# cc1200layoutv_2.net
KiCad netlist of a schematic drawn in EAGLE
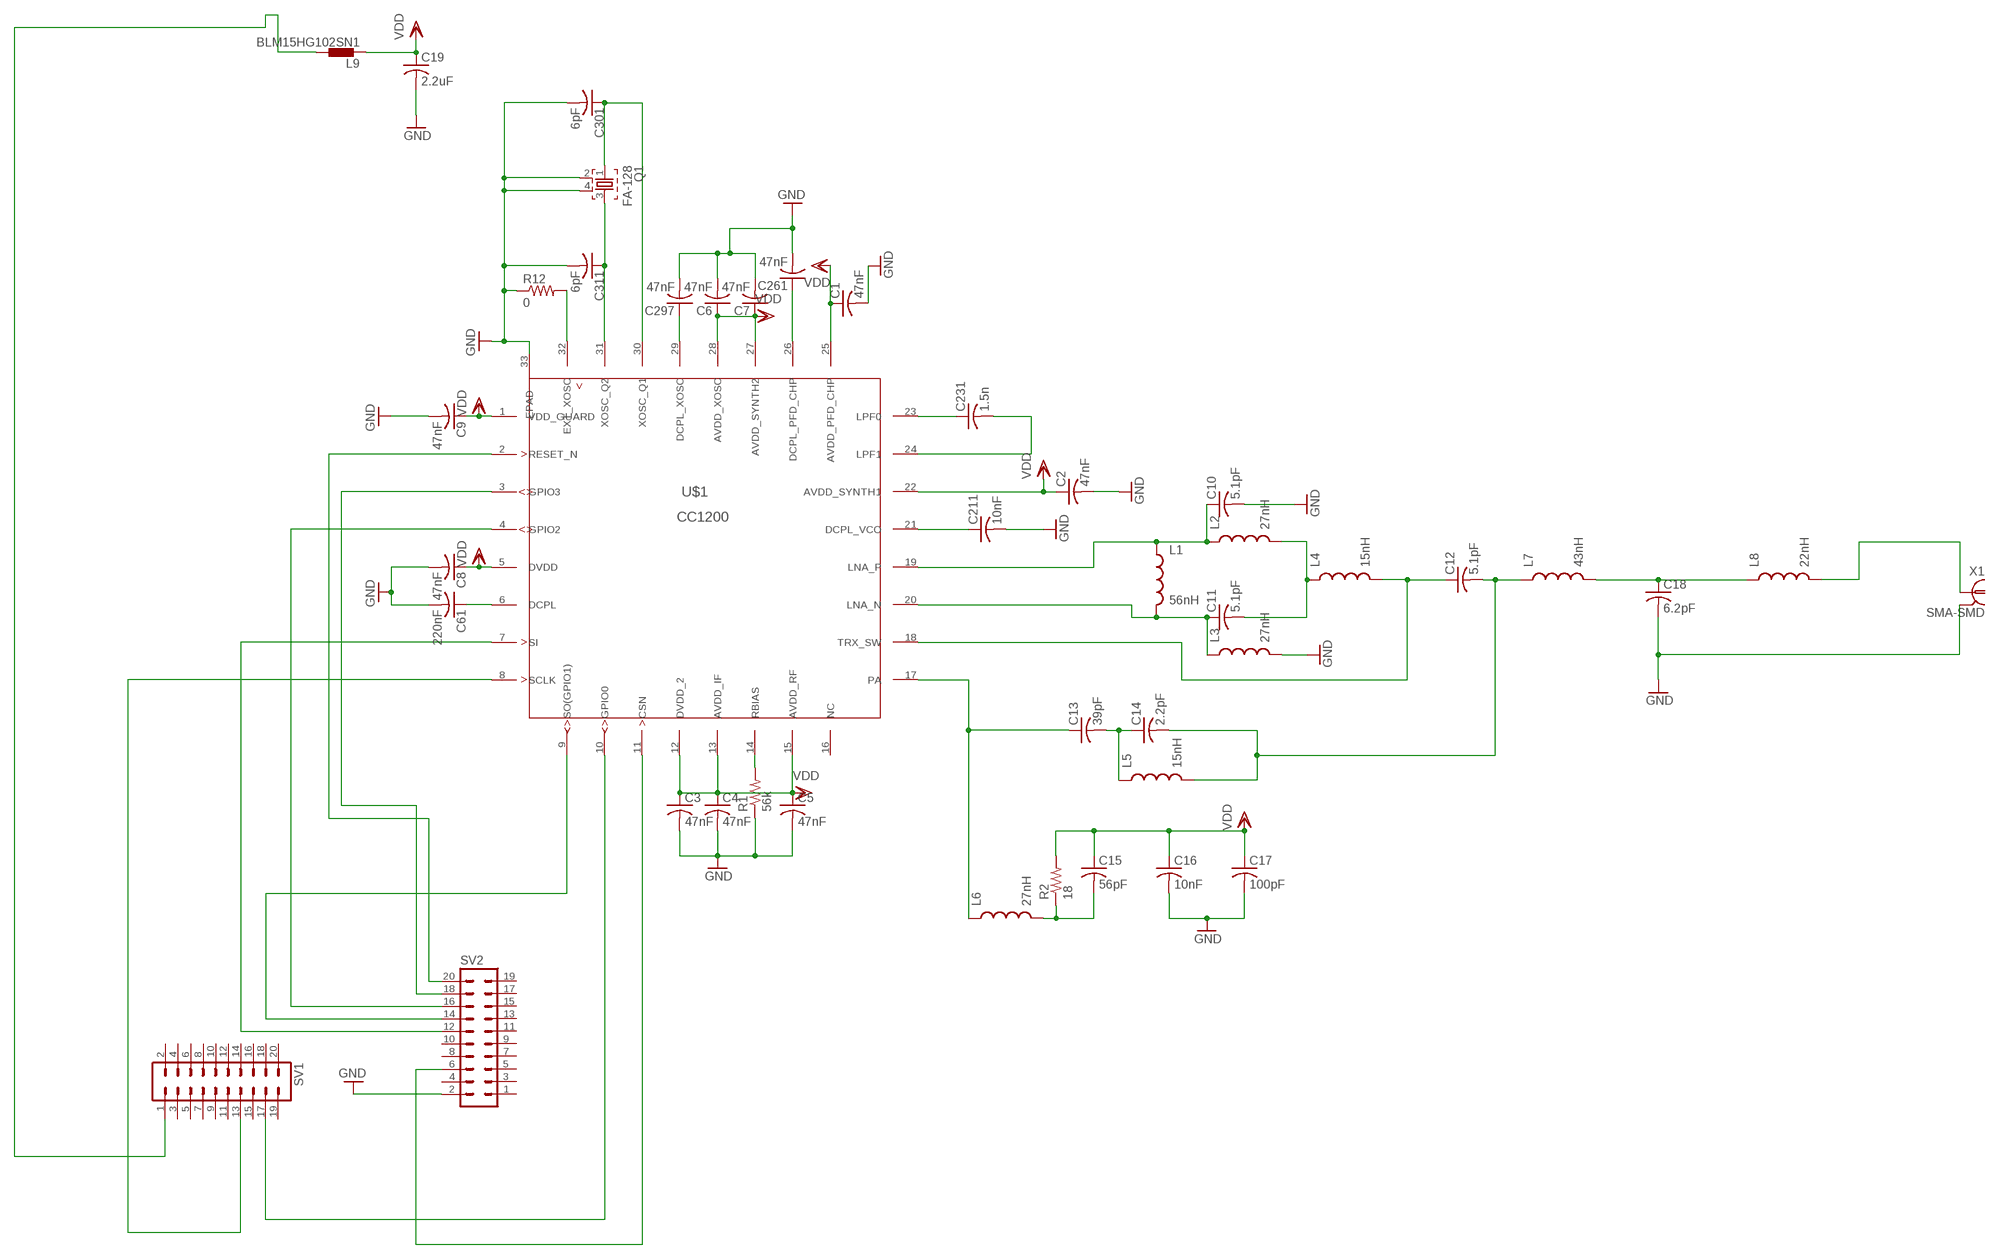
[diagram p0: schematic, sheet 1]

(export (version "E")
  (design (tool "Eeschema 10.0.6"))
  (components
    (comp (ref "C1")
      (value "47nF")
      (footprint "eagle-import:C0402K")
      (libsource (lib "eagle-import") (part "C-USC0402K"))
    )
    (comp (ref "C2")
      (value "47nF")
      (footprint "eagle-import:C0402K")
      (libsource (lib "eagle-import") (part "C-USC0402K"))
    )
    (comp (ref "C3")
      (value "47nF")
      (footprint "eagle-import:C0402K")
      (libsource (lib "eagle-import") (part "C-USC0402K"))
    )
    (comp (ref "C4")
      (value "47nF")
      (footprint "eagle-import:C0402K")
      (libsource (lib "eagle-import") (part "C-USC0402K"))
    )
    (comp (ref "C5")
      (value "47nF")
      (footprint "eagle-import:C0402K")
      (libsource (lib "eagle-import") (part "C-USC0402K"))
    )
    (comp (ref "C6")
      (value "47nF")
      (footprint "eagle-import:C0402K")
      (libsource (lib "eagle-import") (part "C-USC0402K"))
    )
    (comp (ref "C7")
      (value "47nF")
      (footprint "eagle-import:C0402K")
      (libsource (lib "eagle-import") (part "C-USC0402K"))
    )
    (comp (ref "C8")
      (value "47nF")
      (footprint "eagle-import:C0402K")
      (libsource (lib "eagle-import") (part "C-USC0402K"))
    )
    (comp (ref "C9")
      (value "47nF")
      (footprint "eagle-import:C0402K")
      (libsource (lib "eagle-import") (part "C-USC0402K"))
    )
    (comp (ref "C10")
      (value "5.1pF")
      (footprint "eagle-import:C0402K")
      (libsource (lib "eagle-import") (part "C-USC0402K"))
    )
    (comp (ref "C11")
      (value "5.1pF")
      (footprint "eagle-import:C0402K")
      (libsource (lib "eagle-import") (part "C-USC0402K"))
    )
    (comp (ref "C12")
      (value "5.1pF")
      (footprint "eagle-import:C0402K")
      (libsource (lib "eagle-import") (part "C-USC0402K"))
    )
    (comp (ref "C13")
      (value "39pF")
      (footprint "eagle-import:C0402K")
      (libsource (lib "eagle-import") (part "C-USC0402K"))
    )
    (comp (ref "C14")
      (value "2.2pF")
      (footprint "eagle-import:C0402K")
      (libsource (lib "eagle-import") (part "C-USC0402K"))
    )
    (comp (ref "C15")
      (value "56pF")
      (footprint "eagle-import:C0402K")
      (libsource (lib "eagle-import") (part "C-USC0402K"))
    )
    (comp (ref "C16")
      (value "10nF")
      (footprint "eagle-import:C0402K")
      (libsource (lib "eagle-import") (part "C-USC0402K"))
    )
    (comp (ref "C17")
      (value "100pF")
      (footprint "eagle-import:C0402K")
      (libsource (lib "eagle-import") (part "C-USC0402K"))
    )
    (comp (ref "C18")
      (value "6.2pF")
      (footprint "eagle-import:C0402K")
      (libsource (lib "eagle-import") (part "C-USC0402K"))
    )
    (comp (ref "C19")
      (value "2.2uF")
      (footprint "eagle-import:C0603K")
      (libsource (lib "eagle-import") (part "C-USC0603K"))
    )
    (comp (ref "C61")
      (value "220nF")
      (footprint "eagle-import:C0402K")
      (libsource (lib "eagle-import") (part "C-USC0402K"))
    )
    (comp (ref "C211")
      (value "10nF")
      (footprint "eagle-import:C0402K")
      (libsource (lib "eagle-import") (part "C-USC0402K"))
    )
    (comp (ref "C231")
      (value "1.5n")
      (footprint "eagle-import:C0402K")
      (libsource (lib "eagle-import") (part "C-USC0402K"))
    )
    (comp (ref "C261")
      (value "47nF")
      (footprint "eagle-import:C0402K")
      (libsource (lib "eagle-import") (part "C-USC0402K"))
    )
    (comp (ref "C297")
      (value "47nF")
      (footprint "eagle-import:C0402K")
      (libsource (lib "eagle-import") (part "C-USC0402K"))
    )
    (comp (ref "C301")
      (value "6pF")
      (footprint "eagle-import:C0402K")
      (libsource (lib "eagle-import") (part "C-USC0402K"))
    )
    (comp (ref "C311")
      (value "6pF")
      (footprint "eagle-import:C0402K")
      (libsource (lib "eagle-import") (part "C-USC0402K"))
    )
    (comp (ref "L1")
      (value "56nH")
      (footprint "eagle-import:C0402")
      (libsource (lib "eagle-import") (part "INDUCTOR0402"))
    )
    (comp (ref "L2")
      (value "27nH")
      (footprint "eagle-import:C0402")
      (libsource (lib "eagle-import") (part "INDUCTOR0402"))
    )
    (comp (ref "L3")
      (value "27nH")
      (footprint "eagle-import:C0402")
      (libsource (lib "eagle-import") (part "INDUCTOR0402"))
    )
    (comp (ref "L4")
      (value "15nH")
      (footprint "eagle-import:C0402")
      (libsource (lib "eagle-import") (part "INDUCTOR0402"))
    )
    (comp (ref "L5")
      (value "15nH")
      (footprint "eagle-import:C0402")
      (libsource (lib "eagle-import") (part "INDUCTOR0402"))
    )
    (comp (ref "L6")
      (value "27nH")
      (footprint "eagle-import:C0402")
      (libsource (lib "eagle-import") (part "INDUCTOR0402"))
    )
    (comp (ref "L7")
      (value "43nH")
      (footprint "eagle-import:C0402")
      (libsource (lib "eagle-import") (part "INDUCTOR0402"))
    )
    (comp (ref "L8")
      (value "22nH")
      (footprint "eagle-import:C0402")
      (libsource (lib "eagle-import") (part "INDUCTOR0402"))
    )
    (comp (ref "L9")
      (value "BLM15HG102SN1")
      (footprint "eagle-import:0402")
      (libsource (lib "eagle-import") (part "BLM15HG102SN1"))
    )
    (comp (ref "Q1")
      (value "FA-128")
      (footprint "eagle-import:FA-128")
      (libsource (lib "eagle-import") (part "FA-128"))
    )
    (comp (ref "R1")
      (value "56k")
      (footprint "eagle-import:R0402")
      (libsource (lib "eagle-import") (part "R-US_R0402"))
    )
    (comp (ref "R2")
      (value "18")
      (footprint "eagle-import:R0402")
      (libsource (lib "eagle-import") (part "R-US_R0402"))
    )
    (comp (ref "R12")
      (value "0")
      (footprint "eagle-import:R0402")
      (libsource (lib "eagle-import") (part "R-US_R0402"))
    )
    (comp (ref "SV1")
      (value "MA10-2")
      (footprint "eagle-import:MA10-2")
      (libsource (lib "eagle-import") (part "MA10-2"))
    )
    (comp (ref "SV2")
      (value "MA10-2")
      (footprint "eagle-import:MA10-2")
      (libsource (lib "eagle-import") (part "MA10-2"))
    )
    (comp (ref "U$1")
      (value "CC1200")
      (footprint "eagle-import:RHB32_3P45X3P45")
      (libsource (lib "eagle-import") (part "CC1200"))
    )
    (comp (ref "X1")
      (value "SMA-SMD")
      (footprint "eagle-import:SMA-SMD")
      (libsource (lib "eagle-import") (part "SMA-SMD"))
    )
  )
  (nets
    (net (code "1") (name "GND") (class "Default")
      (node (ref "C1") (pin "2") (pinfunction "2_2") (pintype "passive"))
      (node (ref "C10") (pin "2") (pinfunction "2_2") (pintype "passive"))
      (node (ref "C16") (pin "2") (pinfunction "2_2") (pintype "passive"))
      (node (ref "C17") (pin "2") (pinfunction "2_2") (pintype "passive"))
      (node (ref "C18") (pin "2") (pinfunction "2_2") (pintype "passive"))
      (node (ref "C19") (pin "2") (pinfunction "2_2") (pintype "passive"))
      (node (ref "C2") (pin "2") (pinfunction "2_2") (pintype "passive"))
      (node (ref "C211") (pin "2") (pinfunction "2_2") (pintype "passive"))
      (node (ref "C261") (pin "2") (pinfunction "2_2") (pintype "passive"))
      (node (ref "C297") (pin "2") (pinfunction "2_2") (pintype "passive"))
      (node (ref "C3") (pin "2") (pinfunction "2_2") (pintype "passive"))
      (node (ref "C301") (pin "2") (pinfunction "2_2") (pintype "passive"))
      (node (ref "C311") (pin "2") (pinfunction "2_2") (pintype "passive"))
      (node (ref "C4") (pin "2") (pinfunction "2_2") (pintype "passive"))
      (node (ref "C5") (pin "2") (pinfunction "2_2") (pintype "passive"))
      (node (ref "C6") (pin "2") (pinfunction "2_2") (pintype "passive"))
      (node (ref "C61") (pin "2") (pinfunction "2_2") (pintype "passive"))
      (node (ref "C7") (pin "2") (pinfunction "2_2") (pintype "passive"))
      (node (ref "C8") (pin "2") (pinfunction "2_2") (pintype "passive"))
      (node (ref "C9") (pin "2") (pinfunction "2_2") (pintype "passive"))
      (node (ref "L3") (pin "2") (pinfunction "2_2") (pintype "passive"))
      (node (ref "Q1") (pin "2") (pinfunction "2_2") (pintype "passive"))
      (node (ref "Q1") (pin "4") (pinfunction "4_4") (pintype "passive"))
      (node (ref "R1") (pin "1") (pinfunction "1_1") (pintype "passive"))
      (node (ref "R12") (pin "1") (pinfunction "1_1") (pintype "passive"))
      (node (ref "SV2") (pin "2") (pinfunction "2_2") (pintype "passive"))
      (node (ref "U$1") (pin "33") (pinfunction "EPAD_33") (pintype "passive"))
      (node (ref "X1") (pin "2@1") (pinfunction "2_2@1") (pintype "passive"))
      (node (ref "X1") (pin "2@2") (pinfunction "2_2@2") (pintype "passive"))
      (node (ref "X1") (pin "2@3") (pinfunction "2_2@3") (pintype "passive"))
      (node (ref "X1") (pin "2@4") (pinfunction "2_2@4") (pintype "passive"))
      (node (ref "X1") (pin "2@5") (pinfunction "2_2@5") (pintype "passive"))
      (node (ref "X1") (pin "2@6") (pinfunction "2_2@6") (pintype "passive"))
    )
    (net (code "2") (name "Net-(C11-Pad2)") (class "Default")
      (node (ref "C11") (pin "2") (pinfunction "2_2") (pintype "passive"))
      (node (ref "L2") (pin "2") (pinfunction "2_2") (pintype "passive"))
      (node (ref "L4") (pin "1") (pinfunction "1_1") (pintype "passive"))
    )
    (net (code "3") (name "Net-(C12-Pad2)") (class "Default")
      (node (ref "C12") (pin "2") (pinfunction "2_2") (pintype "passive"))
      (node (ref "C14") (pin "2") (pinfunction "2_2") (pintype "passive"))
      (node (ref "L5") (pin "2") (pinfunction "2_2") (pintype "passive"))
      (node (ref "L7") (pin "1") (pinfunction "1_1") (pintype "passive"))
    )
    (net (code "4") (name "Net-(C13-Pad2)") (class "Default")
      (node (ref "C13") (pin "2") (pinfunction "2_2") (pintype "passive"))
      (node (ref "C14") (pin "1") (pinfunction "1_1") (pintype "passive"))
      (node (ref "L5") (pin "1") (pinfunction "1_1") (pintype "passive"))
    )
    (net (code "5") (name "Net-(C15-Pad2)") (class "Default")
      (node (ref "C15") (pin "2") (pinfunction "2_2") (pintype "passive"))
      (node (ref "L6") (pin "2") (pinfunction "2_2") (pintype "passive"))
      (node (ref "R2") (pin "1") (pinfunction "1_1") (pintype "passive"))
    )
    (net (code "6") (name "Net-(C18-Pad1)") (class "Default")
      (node (ref "C18") (pin "1") (pinfunction "1_1") (pintype "passive"))
      (node (ref "L7") (pin "2") (pinfunction "2_2") (pintype "passive"))
      (node (ref "L8") (pin "1") (pinfunction "1_1") (pintype "passive"))
    )
    (net (code "7") (name "Net-(L8-Pad2)") (class "Default")
      (node (ref "L8") (pin "2") (pinfunction "2_2") (pintype "passive"))
      (node (ref "X1") (pin "1") (pinfunction "1_1") (pintype "passive"))
    )
    (net (code "8") (name "Net-(L9-Pad2)") (class "Default")
      (node (ref "L9") (pin "2") (pinfunction "2_2") (pintype "passive"))
      (node (ref "SV1") (pin "1") (pinfunction "1_1") (pintype "passive"))
    )
    (net (code "9") (name "Net-(U$1-CSN)") (class "Default")
      (node (ref "SV2") (pin "6") (pinfunction "6_6") (pintype "passive"))
      (node (ref "U$1") (pin "11") (pinfunction "CSN_11") (pintype "passive"))
    )
    (net (code "10") (name "Net-(U$1-DCPL)") (class "Default")
      (node (ref "C61") (pin "1") (pinfunction "1_1") (pintype "passive"))
      (node (ref "U$1") (pin "6") (pinfunction "DCPL_6") (pintype "passive"))
    )
    (net (code "11") (name "Net-(U$1-DCPL_PFD_CHP)") (class "Default")
      (node (ref "C261") (pin "1") (pinfunction "1_1") (pintype "passive"))
      (node (ref "U$1") (pin "26") (pinfunction "DCPL_PFD_CHP_26") (pintype "passive"))
    )
    (net (code "12") (name "Net-(U$1-DCPL_VCO)") (class "Default")
      (node (ref "C211") (pin "1") (pinfunction "1_1") (pintype "passive"))
      (node (ref "U$1") (pin "21") (pinfunction "DCPL_VCO_21") (pintype "passive"))
    )
    (net (code "13") (name "Net-(U$1-DCPL_XOSC)") (class "Default")
      (node (ref "C297") (pin "1") (pinfunction "1_1") (pintype "passive"))
      (node (ref "U$1") (pin "29") (pinfunction "DCPL_XOSC_29") (pintype "passive"))
    )
    (net (code "14") (name "Net-(U$1-EXT_XOSC)") (class "Default")
      (node (ref "R12") (pin "2") (pinfunction "2_2") (pintype "passive"))
      (node (ref "U$1") (pin "32") (pinfunction "EXT_XOSC_32") (pintype "passive"))
    )
    (net (code "15") (name "Net-(U$1-GPIO0)") (class "Default")
      (node (ref "SV1") (pin "17") (pinfunction "17_17") (pintype "passive"))
      (node (ref "U$1") (pin "10") (pinfunction "GPIO0_10") (pintype "passive"))
    )
    (net (code "16") (name "Net-(U$1-GPIO2)") (class "Default")
      (node (ref "SV2") (pin "16") (pinfunction "16_16") (pintype "passive"))
      (node (ref "U$1") (pin "4") (pinfunction "GPIO2_4") (pintype "passive"))
    )
    (net (code "17") (name "Net-(U$1-GPIO3)") (class "Default")
      (node (ref "SV2") (pin "18") (pinfunction "18_18") (pintype "passive"))
      (node (ref "U$1") (pin "3") (pinfunction "GPIO3_3") (pintype "passive"))
    )
    (net (code "18") (name "Net-(U$1-LNA_N)") (class "Default")
      (node (ref "C11") (pin "1") (pinfunction "1_1") (pintype "passive"))
      (node (ref "L1") (pin "2") (pinfunction "2_2") (pintype "passive"))
      (node (ref "L3") (pin "1") (pinfunction "1_1") (pintype "passive"))
      (node (ref "U$1") (pin "20") (pinfunction "LNA_N_20") (pintype "passive"))
    )
    (net (code "19") (name "Net-(U$1-LNA_P)") (class "Default")
      (node (ref "C10") (pin "1") (pinfunction "1_1") (pintype "passive"))
      (node (ref "L1") (pin "1") (pinfunction "1_1") (pintype "passive"))
      (node (ref "L2") (pin "1") (pinfunction "1_1") (pintype "passive"))
      (node (ref "U$1") (pin "19") (pinfunction "LNA_P_19") (pintype "passive"))
    )
    (net (code "20") (name "Net-(U$1-LPF0)") (class "Default")
      (node (ref "C231") (pin "1") (pinfunction "1_1") (pintype "passive"))
      (node (ref "U$1") (pin "23") (pinfunction "LPF0_23") (pintype "passive"))
    )
    (net (code "21") (name "Net-(U$1-LPF1)") (class "Default")
      (node (ref "C231") (pin "2") (pinfunction "2_2") (pintype "passive"))
      (node (ref "U$1") (pin "24") (pinfunction "LPF1_24") (pintype "passive"))
    )
    (net (code "22") (name "Net-(U$1-PA)") (class "Default")
      (node (ref "C13") (pin "1") (pinfunction "1_1") (pintype "passive"))
      (node (ref "L6") (pin "1") (pinfunction "1_1") (pintype "passive"))
      (node (ref "U$1") (pin "17") (pinfunction "PA_17") (pintype "passive"))
    )
    (net (code "23") (name "Net-(U$1-RBIAS)") (class "Default")
      (node (ref "R1") (pin "2") (pinfunction "2_2") (pintype "passive"))
      (node (ref "U$1") (pin "14") (pinfunction "RBIAS_14") (pintype "passive"))
    )
    (net (code "24") (name "Net-(U$1-RESET_N)") (class "Default")
      (node (ref "SV2") (pin "20") (pinfunction "20_20") (pintype "passive"))
      (node (ref "U$1") (pin "2") (pinfunction "RESET_N_2") (pintype "passive"))
    )
    (net (code "25") (name "Net-(U$1-SCLK)") (class "Default")
      (node (ref "SV1") (pin "13") (pinfunction "13_13") (pintype "passive"))
      (node (ref "U$1") (pin "8") (pinfunction "SCLK_8") (pintype "passive"))
    )
    (net (code "26") (name "Net-(U$1-SI)") (class "Default")
      (node (ref "SV2") (pin "12") (pinfunction "12_12") (pintype "passive"))
      (node (ref "U$1") (pin "7") (pinfunction "SI_7") (pintype "passive"))
    )
    (net (code "27") (name "Net-(U$1-SO(GPIO1))") (class "Default")
      (node (ref "SV2") (pin "14") (pinfunction "14_14") (pintype "passive"))
      (node (ref "U$1") (pin "9") (pinfunction "SO(GPIO1)_9") (pintype "passive"))
    )
    (net (code "28") (name "Net-(U$1-TRX_SW)") (class "Default")
      (node (ref "C12") (pin "1") (pinfunction "1_1") (pintype "passive"))
      (node (ref "L4") (pin "2") (pinfunction "2_2") (pintype "passive"))
      (node (ref "U$1") (pin "18") (pinfunction "TRX_SW_18") (pintype "passive"))
    )
    (net (code "29") (name "Net-(U$1-XOSC_Q1)") (class "Default")
      (node (ref "C301") (pin "1") (pinfunction "1_1") (pintype "passive"))
      (node (ref "Q1") (pin "1") (pinfunction "1_1") (pintype "passive"))
      (node (ref "U$1") (pin "30") (pinfunction "XOSC_Q1_30") (pintype "passive"))
    )
    (net (code "30") (name "Net-(U$1-XOSC_Q2)") (class "Default")
      (node (ref "C311") (pin "1") (pinfunction "1_1") (pintype "passive"))
      (node (ref "Q1") (pin "3") (pinfunction "3_3") (pintype "passive"))
      (node (ref "U$1") (pin "31") (pinfunction "XOSC_Q2_31") (pintype "passive"))
    )
    (net (code "31") (name "VDD") (class "Default")
      (node (ref "C1") (pin "1") (pinfunction "1_1") (pintype "passive"))
      (node (ref "C15") (pin "1") (pinfunction "1_1") (pintype "passive"))
      (node (ref "C16") (pin "1") (pinfunction "1_1") (pintype "passive"))
      (node (ref "C17") (pin "1") (pinfunction "1_1") (pintype "passive"))
      (node (ref "C19") (pin "1") (pinfunction "1_1") (pintype "passive"))
      (node (ref "C2") (pin "1") (pinfunction "1_1") (pintype "passive"))
      (node (ref "C3") (pin "1") (pinfunction "1_1") (pintype "passive"))
      (node (ref "C4") (pin "1") (pinfunction "1_1") (pintype "passive"))
      (node (ref "C5") (pin "1") (pinfunction "1_1") (pintype "passive"))
      (node (ref "C6") (pin "1") (pinfunction "1_1") (pintype "passive"))
      (node (ref "C7") (pin "1") (pinfunction "1_1") (pintype "passive"))
      (node (ref "C8") (pin "1") (pinfunction "1_1") (pintype "passive"))
      (node (ref "C9") (pin "1") (pinfunction "1_1") (pintype "passive"))
      (node (ref "L9") (pin "1") (pinfunction "1_1") (pintype "passive"))
      (node (ref "R2") (pin "2") (pinfunction "2_2") (pintype "passive"))
      (node (ref "U$1") (pin "1") (pinfunction "VDD_GUARD_1") (pintype "passive"))
      (node (ref "U$1") (pin "12") (pinfunction "DVDD_2_12") (pintype "passive"))
      (node (ref "U$1") (pin "13") (pinfunction "AVDD_IF_13") (pintype "passive"))
      (node (ref "U$1") (pin "15") (pinfunction "AVDD_RF_15") (pintype "passive"))
      (node (ref "U$1") (pin "22") (pinfunction "AVDD_SYNTH1_22") (pintype "passive"))
      (node (ref "U$1") (pin "25") (pinfunction "AVDD_PFD_CHP_25") (pintype "passive"))
      (node (ref "U$1") (pin "27") (pinfunction "AVDD_SYNTH2_27") (pintype "passive"))
      (node (ref "U$1") (pin "28") (pinfunction "AVDD_XOSC_28") (pintype "passive"))
      (node (ref "U$1") (pin "5") (pinfunction "DVDD_5") (pintype "passive"))
    )
    (net (code "32") (name "unconnected-(SV1-Pad2)") (class "Default")
      (node (ref "SV1") (pin "2") (pinfunction "2_2") (pintype "passive"))
    )
    (net (code "33") (name "unconnected-(SV1-Pad3)") (class "Default")
      (node (ref "SV1") (pin "3") (pinfunction "3_3") (pintype "passive"))
    )
    (net (code "34") (name "unconnected-(SV1-Pad4)") (class "Default")
      (node (ref "SV1") (pin "4") (pinfunction "4_4") (pintype "passive"))
    )
    (net (code "35") (name "unconnected-(SV1-Pad5)") (class "Default")
      (node (ref "SV1") (pin "5") (pinfunction "5_5") (pintype "passive"))
    )
    (net (code "36") (name "unconnected-(SV1-Pad6)") (class "Default")
      (node (ref "SV1") (pin "6") (pinfunction "6_6") (pintype "passive"))
    )
    (net (code "37") (name "unconnected-(SV1-Pad7)") (class "Default")
      (node (ref "SV1") (pin "7") (pinfunction "7_7") (pintype "passive"))
    )
    (net (code "38") (name "unconnected-(SV1-Pad8)") (class "Default")
      (node (ref "SV1") (pin "8") (pinfunction "8_8") (pintype "passive"))
    )
    (net (code "39") (name "unconnected-(SV1-Pad9)") (class "Default")
      (node (ref "SV1") (pin "9") (pinfunction "9_9") (pintype "passive"))
    )
    (net (code "40") (name "unconnected-(SV1-Pad10)") (class "Default")
      (node (ref "SV1") (pin "10") (pinfunction "10_10") (pintype "passive"))
    )
    (net (code "41") (name "unconnected-(SV1-Pad11)") (class "Default")
      (node (ref "SV1") (pin "11") (pinfunction "11_11") (pintype "passive"))
    )
    (net (code "42") (name "unconnected-(SV1-Pad12)") (class "Default")
      (node (ref "SV1") (pin "12") (pinfunction "12_12") (pintype "passive"))
    )
    (net (code "43") (name "unconnected-(SV1-Pad14)") (class "Default")
      (node (ref "SV1") (pin "14") (pinfunction "14_14") (pintype "passive"))
    )
    (net (code "44") (name "unconnected-(SV1-Pad15)") (class "Default")
      (node (ref "SV1") (pin "15") (pinfunction "15_15") (pintype "passive"))
    )
    (net (code "45") (name "unconnected-(SV1-Pad16)") (class "Default")
      (node (ref "SV1") (pin "16") (pinfunction "16_16") (pintype "passive"))
    )
    (net (code "46") (name "unconnected-(SV1-Pad18)") (class "Default")
      (node (ref "SV1") (pin "18") (pinfunction "18_18") (pintype "passive"))
    )
    (net (code "47") (name "unconnected-(SV1-Pad19)") (class "Default")
      (node (ref "SV1") (pin "19") (pinfunction "19_19") (pintype "passive"))
    )
    (net (code "48") (name "unconnected-(SV1-Pad20)") (class "Default")
      (node (ref "SV1") (pin "20") (pinfunction "20_20") (pintype "passive"))
    )
    (net (code "49") (name "unconnected-(SV2-Pad1)") (class "Default")
      (node (ref "SV2") (pin "1") (pinfunction "1_1") (pintype "passive"))
    )
    (net (code "50") (name "unconnected-(SV2-Pad3)") (class "Default")
      (node (ref "SV2") (pin "3") (pinfunction "3_3") (pintype "passive"))
    )
    (net (code "51") (name "unconnected-(SV2-Pad4)") (class "Default")
      (node (ref "SV2") (pin "4") (pinfunction "4_4") (pintype "passive"))
    )
    (net (code "52") (name "unconnected-(SV2-Pad5)") (class "Default")
      (node (ref "SV2") (pin "5") (pinfunction "5_5") (pintype "passive"))
    )
    (net (code "53") (name "unconnected-(SV2-Pad7)") (class "Default")
      (node (ref "SV2") (pin "7") (pinfunction "7_7") (pintype "passive"))
    )
    (net (code "54") (name "unconnected-(SV2-Pad8)") (class "Default")
      (node (ref "SV2") (pin "8") (pinfunction "8_8") (pintype "passive"))
    )
    (net (code "55") (name "unconnected-(SV2-Pad9)") (class "Default")
      (node (ref "SV2") (pin "9") (pinfunction "9_9") (pintype "passive"))
    )
    (net (code "56") (name "unconnected-(SV2-Pad10)") (class "Default")
      (node (ref "SV2") (pin "10") (pinfunction "10_10") (pintype "passive"))
    )
    (net (code "57") (name "unconnected-(SV2-Pad11)") (class "Default")
      (node (ref "SV2") (pin "11") (pinfunction "11_11") (pintype "passive"))
    )
    (net (code "58") (name "unconnected-(SV2-Pad13)") (class "Default")
      (node (ref "SV2") (pin "13") (pinfunction "13_13") (pintype "passive"))
    )
    (net (code "59") (name "unconnected-(SV2-Pad15)") (class "Default")
      (node (ref "SV2") (pin "15") (pinfunction "15_15") (pintype "passive"))
    )
    (net (code "60") (name "unconnected-(SV2-Pad17)") (class "Default")
      (node (ref "SV2") (pin "17") (pinfunction "17_17") (pintype "passive"))
    )
    (net (code "61") (name "unconnected-(SV2-Pad19)") (class "Default")
      (node (ref "SV2") (pin "19") (pinfunction "19_19") (pintype "passive"))
    )
    (net (code "62") (name "unconnected-(U$1-NC-Pad16)") (class "Default")
      (node (ref "U$1") (pin "16") (pinfunction "NC_16") (pintype "passive"))
    )
  )
)
